# Lab10.net
KiCad netlist of a schematic drawn in Altium Designer
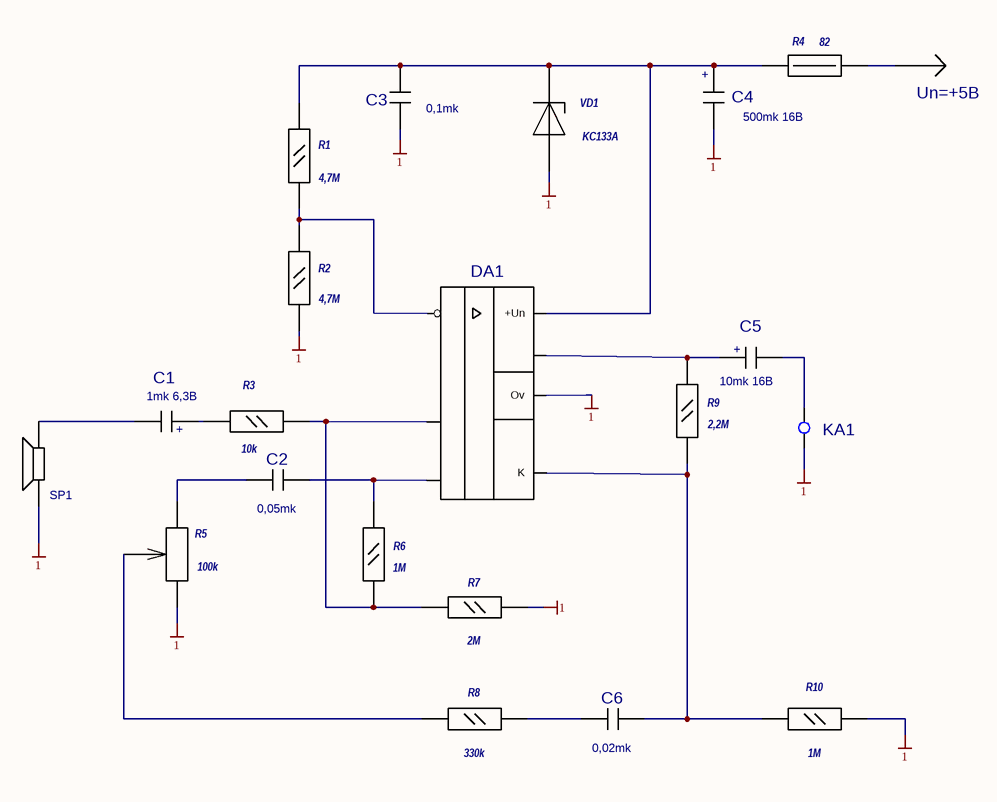
[diagram p0: Lab10.SCHDOC]

(export (version "E")
  (design (tool "Eeschema 10.0.6"))
  (components
    (comp (ref "1")
      (value "Un=+5B")
      (footprint "1PAD")
      (description "XP_1")
      (libsource (lib "*") (part "XP_1"))
    )
    (comp (ref "C1")
      (value "1mk 6,3B")
      (footprint "CAP2")
      (description "CAP2")
      (libsource (lib "*") (part "CAP2"))
    )
    (comp (ref "C2")
      (value "0,05mk")
      (footprint "CAP1")
      (description "CAP1")
      (libsource (lib "*") (part "CAP1"))
    )
    (comp (ref "C3")
      (value "0,1mk")
      (footprint "CAP1")
      (description "CAP1")
      (libsource (lib "*") (part "CAP1"))
    )
    (comp (ref "C4")
      (value "500mk 16B")
      (footprint "CAP2")
      (description "CAP2")
      (libsource (lib "*") (part "CAP2"))
    )
    (comp (ref "C5")
      (value "10mk 16B")
      (footprint "CAP2")
      (description "CAP2")
      (libsource (lib "*") (part "CAP2"))
    )
    (comp (ref "C6")
      (value "0,02mk")
      (footprint "CAP1")
      (description "CAP1")
      (libsource (lib "*") (part "CAP1"))
    )
    (comp (ref "DA1") (value "DIP8") (footprint "DIP8") (libsource (lib "*") (part "DIP8")))
    (comp (ref "KA1") (value "CON2") (footprint "2PAD") (libsource (lib "*") (part "CON2")))
    (comp (ref "R1")
      (value "4,7M")
      (footprint "МЛТ(0.125)")
      (description "МЛТ(0.125)")
      (libsource (lib "*") (part "МЛТ(0.125)"))
    )
    (comp (ref "R2")
      (value "4,7M")
      (footprint "МЛТ(0.125)")
      (description "МЛТ(0.125)")
      (libsource (lib "*") (part "МЛТ(0.125)"))
    )
    (comp (ref "R3")
      (value "10k")
      (footprint "МЛТ(0.125)")
      (description "МЛТ(0.125)")
      (libsource (lib "*") (part "МЛТ(0.125)"))
    )
    (comp (ref "R4")
      (value "82")
      (footprint "МЛТ(0.5)")
      (description "RESISTOR")
      (libsource (lib "*") (part "RESISTOR"))
    )
    (comp (ref "R5")
      (value "100k")
      (footprint "СП3-38В")
      (description "СП3-38В")
      (libsource (lib "*") (part "СП3-38В"))
    )
    (comp (ref "R6")
      (value "1M")
      (footprint "МЛТ(0.125)")
      (description "МЛТ(0.125)")
      (libsource (lib "*") (part "МЛТ(0.125)"))
    )
    (comp (ref "R7")
      (value "2M")
      (footprint "МЛТ(0.125)")
      (description "МЛТ(0.125)")
      (libsource (lib "*") (part "МЛТ(0.125)"))
    )
    (comp (ref "R8")
      (value "330k")
      (footprint "МЛТ(0.125)")
      (description "МЛТ(0.125)")
      (libsource (lib "*") (part "МЛТ(0.125)"))
    )
    (comp (ref "R9")
      (value "2,2M")
      (footprint "МЛТ(0.125)")
      (description "МЛТ(0.125)")
      (libsource (lib "*") (part "МЛТ(0.125)"))
    )
    (comp (ref "R10")
      (value "1M")
      (footprint "МЛТ(0.125)")
      (description "МЛТ(0.125)")
      (libsource (lib "*") (part "МЛТ(0.125)"))
    )
    (comp (ref "SP1") (value "SPEAKER") (footprint "CAP1") (libsource (lib "*") (part "SPEAKER")))
    (comp (ref "VD1") (value "KC133A") (footprint "KC133A") (libsource (lib "*") (part "KC133A")))
  )
  (nets
    (net (code "1") (name "1") (class "Default")
      (node (ref "C3") (pin "1") (pinfunction "1_1") (pintype "passive"))
      (node (ref "C4") (pin "2") (pinfunction "2_2") (pintype "passive"))
      (node (ref "DA1") (pin "6") (pinfunction "Ov_6") (pintype "passive"))
      (node (ref "KA1") (pin "1") (pinfunction "A1_1") (pintype "passive"))
      (node (ref "R10") (pin "2") (pinfunction "2_2") (pintype "passive"))
      (node (ref "R2") (pin "1") (pinfunction "1_1") (pintype "passive"))
      (node (ref "R5") (pin "1") (pinfunction "1_1") (pintype "passive"))
      (node (ref "R7") (pin "1") (pinfunction "1_1") (pintype "passive"))
      (node (ref "SP1") (pin "1") (pintype "passive"))
      (node (ref "VD1") (pin "1") (pinfunction "1_1") (pintype "passive"))
    )
    (net (code "2") (name "Net-(1-A1)") (class "Default")
      (node (ref "1") (pin "1") (pinfunction "A1_1") (pintype "passive"))
      (node (ref "R4") (pin "2") (pinfunction "2_2") (pintype "passive"))
    )
    (net (code "3") (name "Net-(C1-Pad1)") (class "Default")
      (node (ref "C1") (pin "1") (pinfunction "1_1") (pintype "passive"))
      (node (ref "R3") (pin "1") (pinfunction "1_1") (pintype "passive"))
    )
    (net (code "4") (name "Net-(C1-Pad2)") (class "Default")
      (node (ref "C1") (pin "2") (pinfunction "2_2") (pintype "passive"))
      (node (ref "SP1") (pin "2") (pintype "passive"))
    )
    (net (code "5") (name "Net-(C2-Pad1)") (class "Default")
      (node (ref "C2") (pin "1") (pinfunction "1_1") (pintype "passive"))
      (node (ref "R5") (pin "2") (pinfunction "2_2") (pintype "passive"))
    )
    (net (code "6") (name "Net-(C2-Pad2)") (class "Default")
      (node (ref "C2") (pin "2") (pinfunction "2_2") (pintype "passive"))
      (node (ref "DA1") (pin "3") (pinfunction "IN2_3") (pintype "passive"))
      (node (ref "R6") (pin "2") (pinfunction "2_2") (pintype "passive"))
    )
    (net (code "7") (name "Net-(C5-Pad1)") (class "Default")
      (node (ref "C5") (pin "1") (pinfunction "1_1") (pintype "passive"))
      (node (ref "DA1") (pin "5") (pintype "passive"))
      (node (ref "R9") (pin "1") (pinfunction "1_1") (pintype "passive"))
    )
    (net (code "8") (name "Net-(C6-Pad1)") (class "Default")
      (node (ref "C6") (pin "1") (pinfunction "1_1") (pintype "passive"))
      (node (ref "R8") (pin "1") (pinfunction "1_1") (pintype "passive"))
    )
    (net (code "9") (name "Net-(DA1-+Un)") (class "Default")
      (node (ref "C3") (pin "2") (pinfunction "2_2") (pintype "passive"))
      (node (ref "C4") (pin "1") (pinfunction "1_1") (pintype "passive"))
      (node (ref "DA1") (pin "4") (pinfunction "+Un_4") (pintype "passive"))
      (node (ref "R1") (pin "2") (pinfunction "2_2") (pintype "passive"))
      (node (ref "R4") (pin "1") (pinfunction "1_1") (pintype "passive"))
      (node (ref "VD1") (pin "2") (pinfunction "2_2") (pintype "passive"))
    )
    (net (code "10") (name "Net-(DA1-IN1)") (class "Default")
      (node (ref "DA1") (pin "1") (pinfunction "IN1_1") (pintype "passive"))
      (node (ref "R1") (pin "1") (pinfunction "1_1") (pintype "passive"))
      (node (ref "R2") (pin "2") (pinfunction "2_2") (pintype "passive"))
    )
    (net (code "11") (name "Net-(DA1-IN2-Pad2)") (class "Default")
      (node (ref "DA1") (pin "2") (pinfunction "IN2_2") (pintype "passive"))
      (node (ref "R3") (pin "2") (pinfunction "2_2") (pintype "passive"))
      (node (ref "R6") (pin "1") (pinfunction "1_1") (pintype "passive"))
      (node (ref "R7") (pin "2") (pinfunction "2_2") (pintype "passive"))
    )
    (net (code "12") (name "Net-(DA1-K)") (class "Default")
      (node (ref "C6") (pin "2") (pinfunction "2_2") (pintype "passive"))
      (node (ref "DA1") (pin "7") (pinfunction "K_7") (pintype "passive"))
      (node (ref "R10") (pin "1") (pinfunction "1_1") (pintype "passive"))
      (node (ref "R9") (pin "2") (pinfunction "2_2") (pintype "passive"))
    )
    (net (code "13") (name "Net-(KA1-A2)") (class "Default")
      (node (ref "C5") (pin "2") (pinfunction "2_2") (pintype "passive"))
      (node (ref "KA1") (pin "2") (pinfunction "A2_2") (pintype "passive"))
    )
    (net (code "14") (name "Net-(R5-Pad3)") (class "Default")
      (node (ref "R5") (pin "3") (pinfunction "3_3") (pintype "passive"))
      (node (ref "R8") (pin "2") (pinfunction "2_2") (pintype "passive"))
    )
    (net (code "15") (name "unconnected-(DA1-GND-PadPWR)") (class "Default")
      (node (ref "DA1") (pin "PWR") (pinfunction "GND_PWR") (pintype "passive"))
    )
  )
)
